# Power.net
KiCad netlist of a schematic drawn in Altium Designer
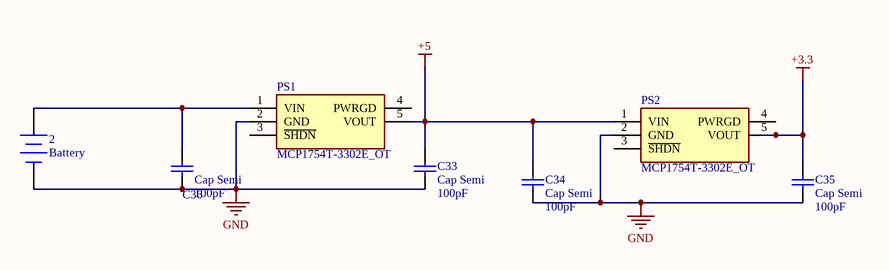
[diagram p0: Power.SchDoc]

(export (version "E")
  (design (tool "Eeschema 10.0.6"))
  (components
    (comp (ref "2")
      (value "Battery")
      (footprint "BAT-2")
      (description "Multicell Battery")
      (fields (field (name "PUBLISHER") "Altium Limited"))
      (libsource (lib "Miscellaneous Devices") (part "Battery"))
    )
    (comp (ref "C33")
      (value "Cap Semi")
      (footprint "0805c")
      (description "Capacitor (Semiconductor SIM Model)")
      (fields (field (name "ALTIUM_VALUE") "100pF") (field (name "PUBLISHER") "Altium Limited"))
      (libsource (lib "Miscellaneous Devices") (part "Cap Semi"))
    )
    (comp (ref "C34")
      (value "Cap Semi")
      (footprint "0805c")
      (description "Capacitor (Semiconductor SIM Model)")
      (fields (field (name "ALTIUM_VALUE") "100pF") (field (name "PUBLISHER") "Altium Limited"))
      (libsource (lib "Miscellaneous Devices") (part "Cap Semi"))
    )
    (comp (ref "C35")
      (value "Cap Semi")
      (footprint "0805c")
      (description "Capacitor (Semiconductor SIM Model)")
      (fields (field (name "ALTIUM_VALUE") "100pF") (field (name "PUBLISHER") "Altium Limited"))
      (libsource (lib "Miscellaneous Devices") (part "Cap Semi"))
    )
    (comp (ref "C36")
      (value "Cap Semi")
      (footprint "0805c")
      (description "Capacitor (Semiconductor SIM Model)")
      (fields (field (name "ALTIUM_VALUE") "100pF") (field (name "PUBLISHER") "Altium Limited"))
      (libsource (lib "Miscellaneous Devices") (part "Cap Semi"))
    )
    (comp (ref "PS1")
      (value "MCP1754T-3302E_OT")
      (footprint "SOT23-5")
      (description "Power Supply")
      (fields
        (field (name "MANUFACTURER_PART_NUMBER") "MCP1754T-3302E/OT")
        (field (name "MOUSER PART NUMBER") "579-MCP1754T3302EOT")
      )
      (libsource (lib "*") (part "MCP1754T-3302E_OT"))
    )
    (comp (ref "PS2")
      (value "MCP1754T-3302E_OT")
      (footprint "SOT23-5")
      (description "Power Supply")
      (fields
        (field (name "MANUFACTURER_PART_NUMBER") "MCP1754T-3302E/OT")
        (field (name "MOUSER PART NUMBER") "579-MCP1754T3302EOT")
      )
      (libsource (lib "*") (part "MCP1754T-3302E_OT"))
    )
  )
  (nets
    (net (code "1") (name "+3.3") (class "Default")
      (node (ref "C35") (pin "1") (pinfunction "1_1") (pintype "passive"))
      (node (ref "PS2") (pin "5") (pinfunction "VOUT_5") (pintype "passive"))
    )
    (net (code "2") (name "+5") (class "Default")
      (node (ref "C33") (pin "1") (pinfunction "1_1") (pintype "passive"))
      (node (ref "C34") (pin "2") (pinfunction "2_2") (pintype "passive"))
      (node (ref "PS1") (pin "5") (pinfunction "VOUT_5") (pintype "passive"))
      (node (ref "PS2") (pin "1") (pinfunction "VIN_1") (pintype "passive"))
    )
    (net (code "3") (name "GND") (class "Default")
      (node (ref "2") (pin "2") (pinfunction "-_2") (pintype "passive"))
      (node (ref "C33") (pin "2") (pinfunction "2_2") (pintype "passive"))
      (node (ref "C34") (pin "1") (pinfunction "1_1") (pintype "passive"))
      (node (ref "C35") (pin "2") (pinfunction "2_2") (pintype "passive"))
      (node (ref "C36") (pin "1") (pinfunction "1_1") (pintype "passive"))
      (node (ref "PS1") (pin "2") (pinfunction "GND_2") (pintype "passive"))
      (node (ref "PS2") (pin "2") (pinfunction "GND_2") (pintype "passive"))
    )
    (net (code "4") (name "Net-(2-+)") (class "Default")
      (node (ref "2") (pin "1") (pinfunction "+_1") (pintype "passive"))
      (node (ref "C36") (pin "2") (pinfunction "2_2") (pintype "passive"))
      (node (ref "PS1") (pin "1") (pinfunction "VIN_1") (pintype "passive"))
    )
    (net (code "5") (name "unconnected-(PS1-PWRGD-Pad4)") (class "Default")
      (node (ref "PS1") (pin "4") (pinfunction "PWRGD_4") (pintype "passive"))
    )
    (net (code "6") (name "unconnected-(PS1-~{SHDN}-Pad3)") (class "Default")
      (node (ref "PS1") (pin "3") (pinfunction "~{SHDN}_3") (pintype "passive"))
    )
    (net (code "7") (name "unconnected-(PS2-PWRGD-Pad4)") (class "Default")
      (node (ref "PS2") (pin "4") (pinfunction "PWRGD_4") (pintype "passive"))
    )
    (net (code "8") (name "unconnected-(PS2-~{SHDN}-Pad3)") (class "Default")
      (node (ref "PS2") (pin "3") (pinfunction "~{SHDN}_3") (pintype "passive"))
    )
  )
)
